# 1-Schematic_LABBOX_V3.net
KiCad netlist of a schematic drawn in EasyEDA
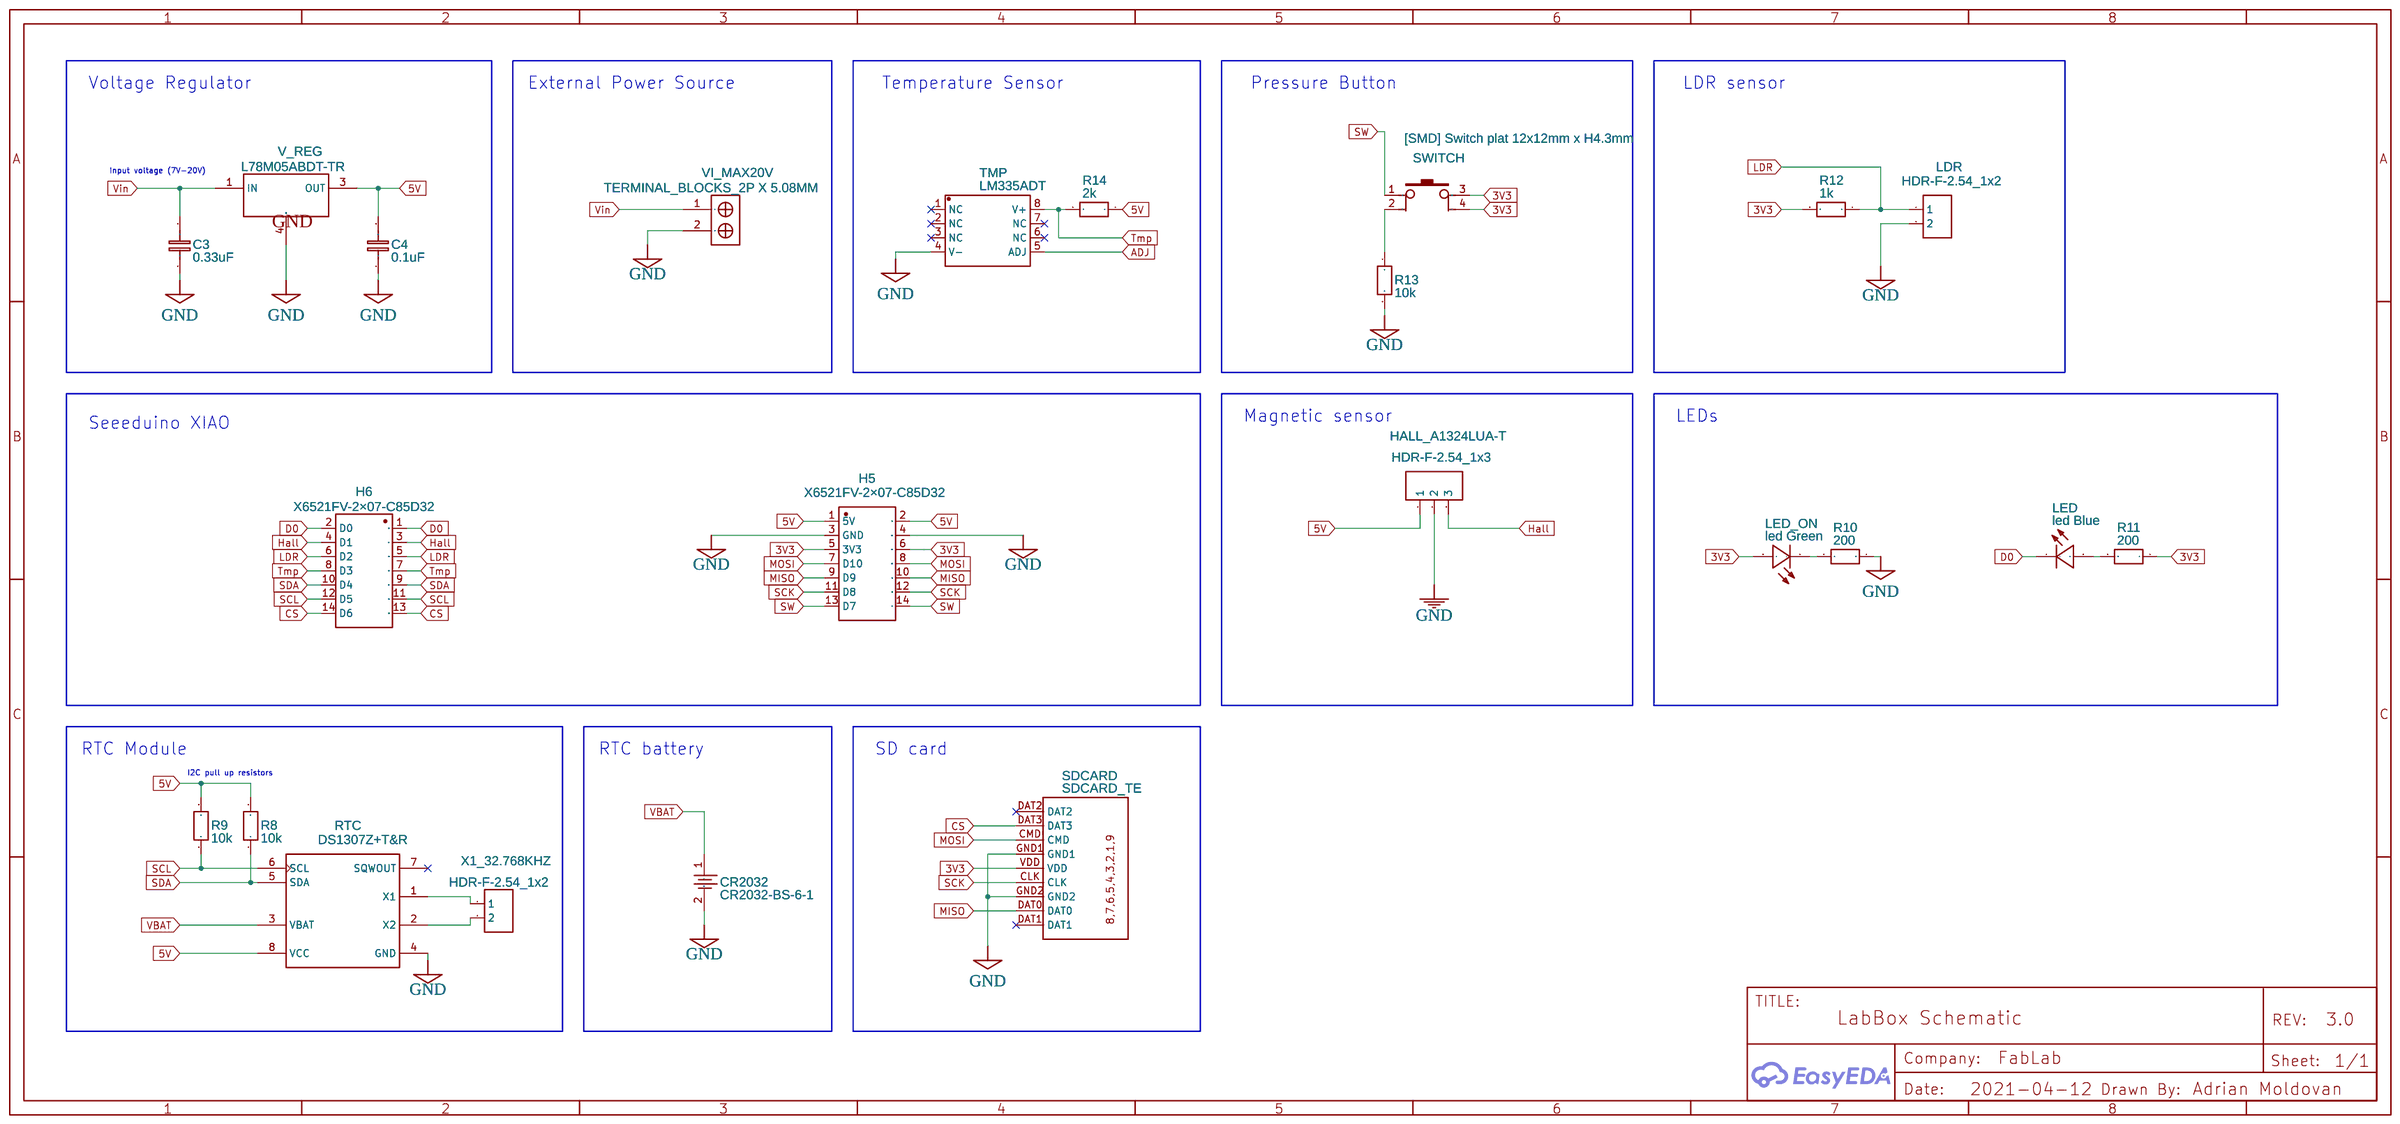
[diagram p0: schematic sheet]

(export (version "E")
  (design (tool "Eeschema 10.0.6"))
  (components
    (comp (ref "C3") (value "0.33uF") (libsource (lib "") (part "C_1206_EU")))
    (comp (ref "C4") (value "0.1uF") (libsource (lib "") (part "C_1206_EU_1")))
    (comp (ref "CR2032")
      (value "CR2032-BS-6-1")
      (fields (field (name "BOM_Supplier Part") "C70377"))
      (libsource (lib "") (part "CR2032-BS-6-1"))
    )
    (comp (ref "H5")
      (value "X6521FV-2×07-C85D32")
      (fields (field (name "BOM_Supplier Part") "C718229"))
      (libsource (lib "") (part "X6521FV-2×07-C85D32_1"))
    )
    (comp (ref "H6")
      (value "X6521FV-2×07-C85D32")
      (fields (field (name "BOM_Supplier Part") "C718229"))
      (libsource (lib "") (part "X6521FV-2×07-C85D32"))
    )
    (comp (ref "HALL_A1324LUA-T")
      (value "HDR-F-2.54_1x3")
      (fields (field (name "BOM_Supplier Part") "C146690"))
      (libsource (lib "") (part "HDR-F-2.54_1x3"))
    )
    (comp (ref "LDR")
      (value "HDR-F-2.54_1x2")
      (fields (field (name "BOM_Supplier Part") "C49661"))
      (libsource (lib "") (part "HDR-F-2.54_1x2"))
    )
    (comp (ref "LED")
      (value "led Blue")
      (fields (field (name "BOM_Manufacturer Part") "led Green") (field (name "BOM_Supplier Part") "C14641"))
      (libsource (lib "") (part "led Green"))
    )
    (comp (ref "LED_ON")
      (value "led Green")
      (fields (field (name "BOM_Supplier Part") "C14641"))
      (libsource (lib "") (part "led Green_1"))
    )
    (comp (ref "R8") (value "10k") (libsource (lib "") (part "R_1206_EU")))
    (comp (ref "R9") (value "10k") (libsource (lib "") (part "R_1206_EU")))
    (comp (ref "R10") (value "200") (libsource (lib "") (part "R_1206_EU_1")))
    (comp (ref "R11") (value "200") (libsource (lib "") (part "R_1206_EU_1")))
    (comp (ref "R12") (value "1k") (libsource (lib "") (part "R_1206_EU_1")))
    (comp (ref "R13") (value "10k") (libsource (lib "") (part "R_1206_EU_2")))
    (comp (ref "R14") (value "2k") (libsource (lib "") (part "R_1206_EU_1")))
    (comp (ref "RTC")
      (value "DS1307Z+T&R")
      (fields (field (name "BOM_Supplier Part") "C9868"))
      (libsource (lib "") (part "DS1307Z+T&amp;amp;R"))
    )
    (comp (ref "SDCARD") (value "SDCARD_TE") (libsource (lib "") (part "SDCARD_TE")))
    (comp (ref "SWITCH")
      (value "[SMD] Switch plat 12x12mm x H4.3mm")
      (fields (field (name "BOM_Supplier Part") "C410376"))
      (libsource (lib "") (part "[SMD] Switch plat 12x12mm x H4.3mm"))
    )
    (comp (ref "TMP")
      (value "LM335ADT")
      (fields (field (name "BOM_Supplier Part") "C361027"))
      (libsource (lib "") (part "LM335ADT"))
    )
    (comp (ref "VI_MAX20V")
      (value "TERMINAL_BLOCKS_2P X 5.08MM")
      (fields
        (field (name "BOM_Manufacturer Part") "Terminal Block")
        (field (name "BOM_Supplier Part") "undefined")
      )
      (libsource (lib "") (part "TERMINAL_BLOCKS_2P X 5.08MM"))
    )
    (comp (ref "V_REG")
      (value "L78M05ABDT-TR")
      (fields (field (name "BOM_Supplier Part") "C58069"))
      (libsource (lib "") (part "L78M05ABDT-TR"))
    )
    (comp (ref "X1_32.768KHZ")
      (value "HDR-F-2.54_1x2")
      (fields (field (name "BOM_Supplier Part") "C49661"))
      (libsource (lib "") (part "HDR-F-2.54_1x2_1"))
    )
  )
  (nets
    (net (code "1") (name "3V3") (class "Default")
      (node (ref "H5") (pin "5") (pinfunction "3V3_5") (pintype "unspecified"))
      (node (ref "H5") (pin "6") (pinfunction "3V3_6") (pintype "unspecified"))
      (node (ref "LED_ON") (pin "2") (pinfunction "+_2") (pintype "unspecified"))
      (node (ref "R11") (pin "1") (pinfunction "1_1") (pintype "unspecified"))
      (node (ref "R12") (pin "2") (pinfunction "2_2") (pintype "unspecified"))
      (node (ref "SDCARD") (pin "VDD") (pinfunction "VDD_VDD") (pintype "bidirectional"))
      (node (ref "SWITCH") (pin "3") (pinfunction "3_3") (pintype "input"))
      (node (ref "SWITCH") (pin "4") (pinfunction "4_4") (pintype "input"))
    )
    (net (code "2") (name "5V") (class "Default")
      (node (ref "C4") (pin "2") (pinfunction "2_2") (pintype "unspecified"))
      (node (ref "H5") (pin "1") (pinfunction "5V_1") (pintype "unspecified"))
      (node (ref "H5") (pin "2") (pinfunction "5V_2") (pintype "unspecified"))
      (node (ref "HALL_A1324LUA-T") (pin "1") (pinfunction "1_1") (pintype "input"))
      (node (ref "R14") (pin "1") (pinfunction "1_1") (pintype "unspecified"))
      (node (ref "R8") (pin "2") (pinfunction "2_2") (pintype "unspecified"))
      (node (ref "R9") (pin "2") (pinfunction "2_2") (pintype "unspecified"))
      (node (ref "RTC") (pin "8") (pinfunction "VCC_8") (pintype "passive"))
      (node (ref "V_REG") (pin "3") (pinfunction "OUT_3") (pintype "passive"))
    )
    (net (code "3") (name "ADJ") (class "Default")
      (node (ref "TMP") (pin "5") (pinfunction "ADJ_5") (pintype "unspecified"))
    )
    (net (code "4") (name "CS") (class "Default")
      (node (ref "H6") (pin "13") (pinfunction "D6_13") (pintype "unspecified"))
      (node (ref "H6") (pin "14") (pinfunction "D6_14") (pintype "unspecified"))
      (node (ref "SDCARD") (pin "DAT3") (pinfunction "DAT3_DAT3") (pintype "bidirectional"))
    )
    (net (code "5") (name "D0") (class "Default")
      (node (ref "H6") (pin "1") (pinfunction "D0_1") (pintype "unspecified"))
      (node (ref "H6") (pin "2") (pinfunction "D0_2") (pintype "unspecified"))
      (node (ref "LED") (pin "1") (pinfunction "-_1") (pintype "unspecified"))
    )
    (net (code "6") (name "GND") (class "Default")
      (node (ref "C3") (pin "1") (pinfunction "1_1") (pintype "unspecified"))
      (node (ref "C4") (pin "1") (pinfunction "1_1") (pintype "unspecified"))
      (node (ref "CR2032") (pin "2") (pinfunction "2_2") (pintype "input"))
      (node (ref "H5") (pin "3") (pinfunction "GND_3") (pintype "unspecified"))
      (node (ref "H5") (pin "4") (pinfunction "GND_4") (pintype "unspecified"))
      (node (ref "HALL_A1324LUA-T") (pin "2") (pinfunction "2_2") (pintype "input"))
      (node (ref "LDR") (pin "2") (pinfunction "2_2") (pintype "input"))
      (node (ref "R10") (pin "1") (pinfunction "1_1") (pintype "unspecified"))
      (node (ref "R13") (pin "2") (pinfunction "2_2") (pintype "unspecified"))
      (node (ref "RTC") (pin "4") (pinfunction "GND_4") (pintype "passive"))
      (node (ref "SDCARD") (pin "GND1") (pinfunction "GND1_GND1") (pintype "bidirectional"))
      (node (ref "SDCARD") (pin "GND2") (pinfunction "GND2_GND2") (pintype "bidirectional"))
      (node (ref "TMP") (pin "4") (pinfunction "V-_4") (pintype "unspecified"))
      (node (ref "VI_MAX20V") (pin "2") (pinfunction "2_2") (pintype "unspecified"))
      (node (ref "V_REG") (pin "4") (pinfunction "GND_4") (pintype "passive"))
    )
    (net (code "7") (name "Hall") (class "Default")
      (node (ref "H6") (pin "3") (pinfunction "D1_3") (pintype "unspecified"))
      (node (ref "H6") (pin "4") (pinfunction "D1_4") (pintype "unspecified"))
      (node (ref "HALL_A1324LUA-T") (pin "3") (pinfunction "3_3") (pintype "input"))
    )
    (net (code "8") (name "LDR") (class "Default")
      (node (ref "H6") (pin "5") (pinfunction "D2_5") (pintype "unspecified"))
      (node (ref "H6") (pin "6") (pinfunction "D2_6") (pintype "unspecified"))
      (node (ref "LDR") (pin "1") (pinfunction "1_1") (pintype "input"))
      (node (ref "R12") (pin "1") (pinfunction "1_1") (pintype "unspecified"))
    )
    (net (code "9") (name "MISO") (class "Default")
      (node (ref "H5") (pin "10") (pinfunction "D9_10") (pintype "unspecified"))
      (node (ref "H5") (pin "9") (pinfunction "D9_9") (pintype "unspecified"))
      (node (ref "SDCARD") (pin "DAT0") (pinfunction "DAT0_DAT0") (pintype "bidirectional"))
    )
    (net (code "10") (name "MOSI") (class "Default")
      (node (ref "H5") (pin "7") (pinfunction "D10_7") (pintype "unspecified"))
      (node (ref "H5") (pin "8") (pinfunction "D10_8") (pintype "unspecified"))
      (node (ref "SDCARD") (pin "CMD") (pinfunction "CMD_CMD") (pintype "bidirectional"))
    )
    (net (code "11") (name "Net-(LED-+)") (class "Default")
      (node (ref "LED") (pin "2") (pinfunction "+_2") (pintype "unspecified"))
      (node (ref "R11") (pin "2") (pinfunction "2_2") (pintype "unspecified"))
    )
    (net (code "12") (name "Net-(LED_ON--)") (class "Default")
      (node (ref "LED_ON") (pin "1") (pinfunction "-_1") (pintype "unspecified"))
      (node (ref "R10") (pin "2") (pinfunction "2_2") (pintype "unspecified"))
    )
    (net (code "13") (name "Net-(R13-Pad1)") (class "Default")
      (node (ref "R13") (pin "1") (pinfunction "1_1") (pintype "unspecified"))
      (node (ref "SWITCH") (pin "2") (pinfunction "2_2") (pintype "input"))
    )
    (net (code "14") (name "Net-(RTC-X1)") (class "Default")
      (node (ref "RTC") (pin "1") (pinfunction "X1_1") (pintype "unspecified"))
      (node (ref "X1_32.768KHZ") (pin "1") (pinfunction "1_1") (pintype "input"))
    )
    (net (code "15") (name "Net-(RTC-X2)") (class "Default")
      (node (ref "RTC") (pin "2") (pinfunction "X2_2") (pintype "unspecified"))
      (node (ref "X1_32.768KHZ") (pin "2") (pinfunction "2_2") (pintype "input"))
    )
    (net (code "16") (name "SCK") (class "Default")
      (node (ref "H5") (pin "11") (pinfunction "D8_11") (pintype "unspecified"))
      (node (ref "H5") (pin "12") (pinfunction "D8_12") (pintype "unspecified"))
      (node (ref "SDCARD") (pin "CLK") (pinfunction "CLK_CLK") (pintype "bidirectional"))
    )
    (net (code "17") (name "SCL") (class "Default")
      (node (ref "H6") (pin "11") (pinfunction "D5_11") (pintype "unspecified"))
      (node (ref "H6") (pin "12") (pinfunction "D5_12") (pintype "unspecified"))
      (node (ref "R9") (pin "1") (pinfunction "1_1") (pintype "unspecified"))
      (node (ref "RTC") (pin "6") (pinfunction "SCL_6") (pintype "unspecified"))
    )
    (net (code "18") (name "SDA") (class "Default")
      (node (ref "H6") (pin "10") (pinfunction "D4_10") (pintype "unspecified"))
      (node (ref "H6") (pin "9") (pinfunction "D4_9") (pintype "unspecified"))
      (node (ref "R8") (pin "1") (pinfunction "1_1") (pintype "unspecified"))
      (node (ref "RTC") (pin "5") (pinfunction "SDA_5") (pintype "bidirectional"))
    )
    (net (code "19") (name "SW") (class "Default")
      (node (ref "H5") (pin "13") (pinfunction "D7_13") (pintype "unspecified"))
      (node (ref "H5") (pin "14") (pinfunction "14_14") (pintype "unspecified"))
      (node (ref "SWITCH") (pin "1") (pinfunction "1_1") (pintype "input"))
    )
    (net (code "20") (name "Tmp") (class "Default")
      (node (ref "H6") (pin "7") (pinfunction "D3_7") (pintype "unspecified"))
      (node (ref "H6") (pin "8") (pinfunction "D3_8") (pintype "unspecified"))
      (node (ref "R14") (pin "2") (pinfunction "2_2") (pintype "unspecified"))
      (node (ref "TMP") (pin "8") (pinfunction "V+_8") (pintype "unspecified"))
    )
    (net (code "21") (name "VBAT") (class "Default")
      (node (ref "CR2032") (pin "1") (pinfunction "1_1") (pintype "input"))
      (node (ref "RTC") (pin "3") (pinfunction "VBAT_3") (pintype "passive"))
    )
    (net (code "22") (name "Vin") (class "Default")
      (node (ref "C3") (pin "2") (pinfunction "2_2") (pintype "unspecified"))
      (node (ref "VI_MAX20V") (pin "1") (pinfunction "1_1") (pintype "unspecified"))
      (node (ref "V_REG") (pin "1") (pinfunction "IN_1") (pintype "passive"))
    )
    (net (code "23") (name "unconnected-(RTC-SQWOUT-Pad7)") (class "Default")
      (node (ref "RTC") (pin "7") (pinfunction "SQWOUT_7") (pintype "unspecified+no_connect"))
    )
    (net (code "24") (name "unconnected-(SDCARD-PadDAT1)") (class "Default")
      (node (ref "SDCARD") (pin "DAT1") (pinfunction "DAT1_DAT1") (pintype "bidirectional+no_connect"))
    )
    (net (code "25") (name "unconnected-(SDCARD-PadDAT2)") (class "Default")
      (node (ref "SDCARD") (pin "DAT2") (pinfunction "DAT2_DAT2") (pintype "bidirectional+no_connect"))
    )
    (net (code "26") (name "unconnected-(TMP-NC-Pad1)") (class "Default")
      (node (ref "TMP") (pin "1") (pinfunction "NC_1") (pintype "unspecified+no_connect"))
    )
    (net (code "27") (name "unconnected-(TMP-NC-Pad2)") (class "Default")
      (node (ref "TMP") (pin "2") (pinfunction "NC_2") (pintype "unspecified+no_connect"))
    )
    (net (code "28") (name "unconnected-(TMP-NC-Pad3)") (class "Default")
      (node (ref "TMP") (pin "3") (pinfunction "NC_3") (pintype "unspecified+no_connect"))
    )
    (net (code "29") (name "unconnected-(TMP-NC-Pad6)") (class "Default")
      (node (ref "TMP") (pin "6") (pinfunction "NC_6") (pintype "unspecified+no_connect"))
    )
    (net (code "30") (name "unconnected-(TMP-NC-Pad7)") (class "Default")
      (node (ref "TMP") (pin "7") (pinfunction "NC_7") (pintype "unspecified+no_connect"))
    )
  )
)
